# DCMv3.net
KiCad netlist of a schematic drawn in EAGLE
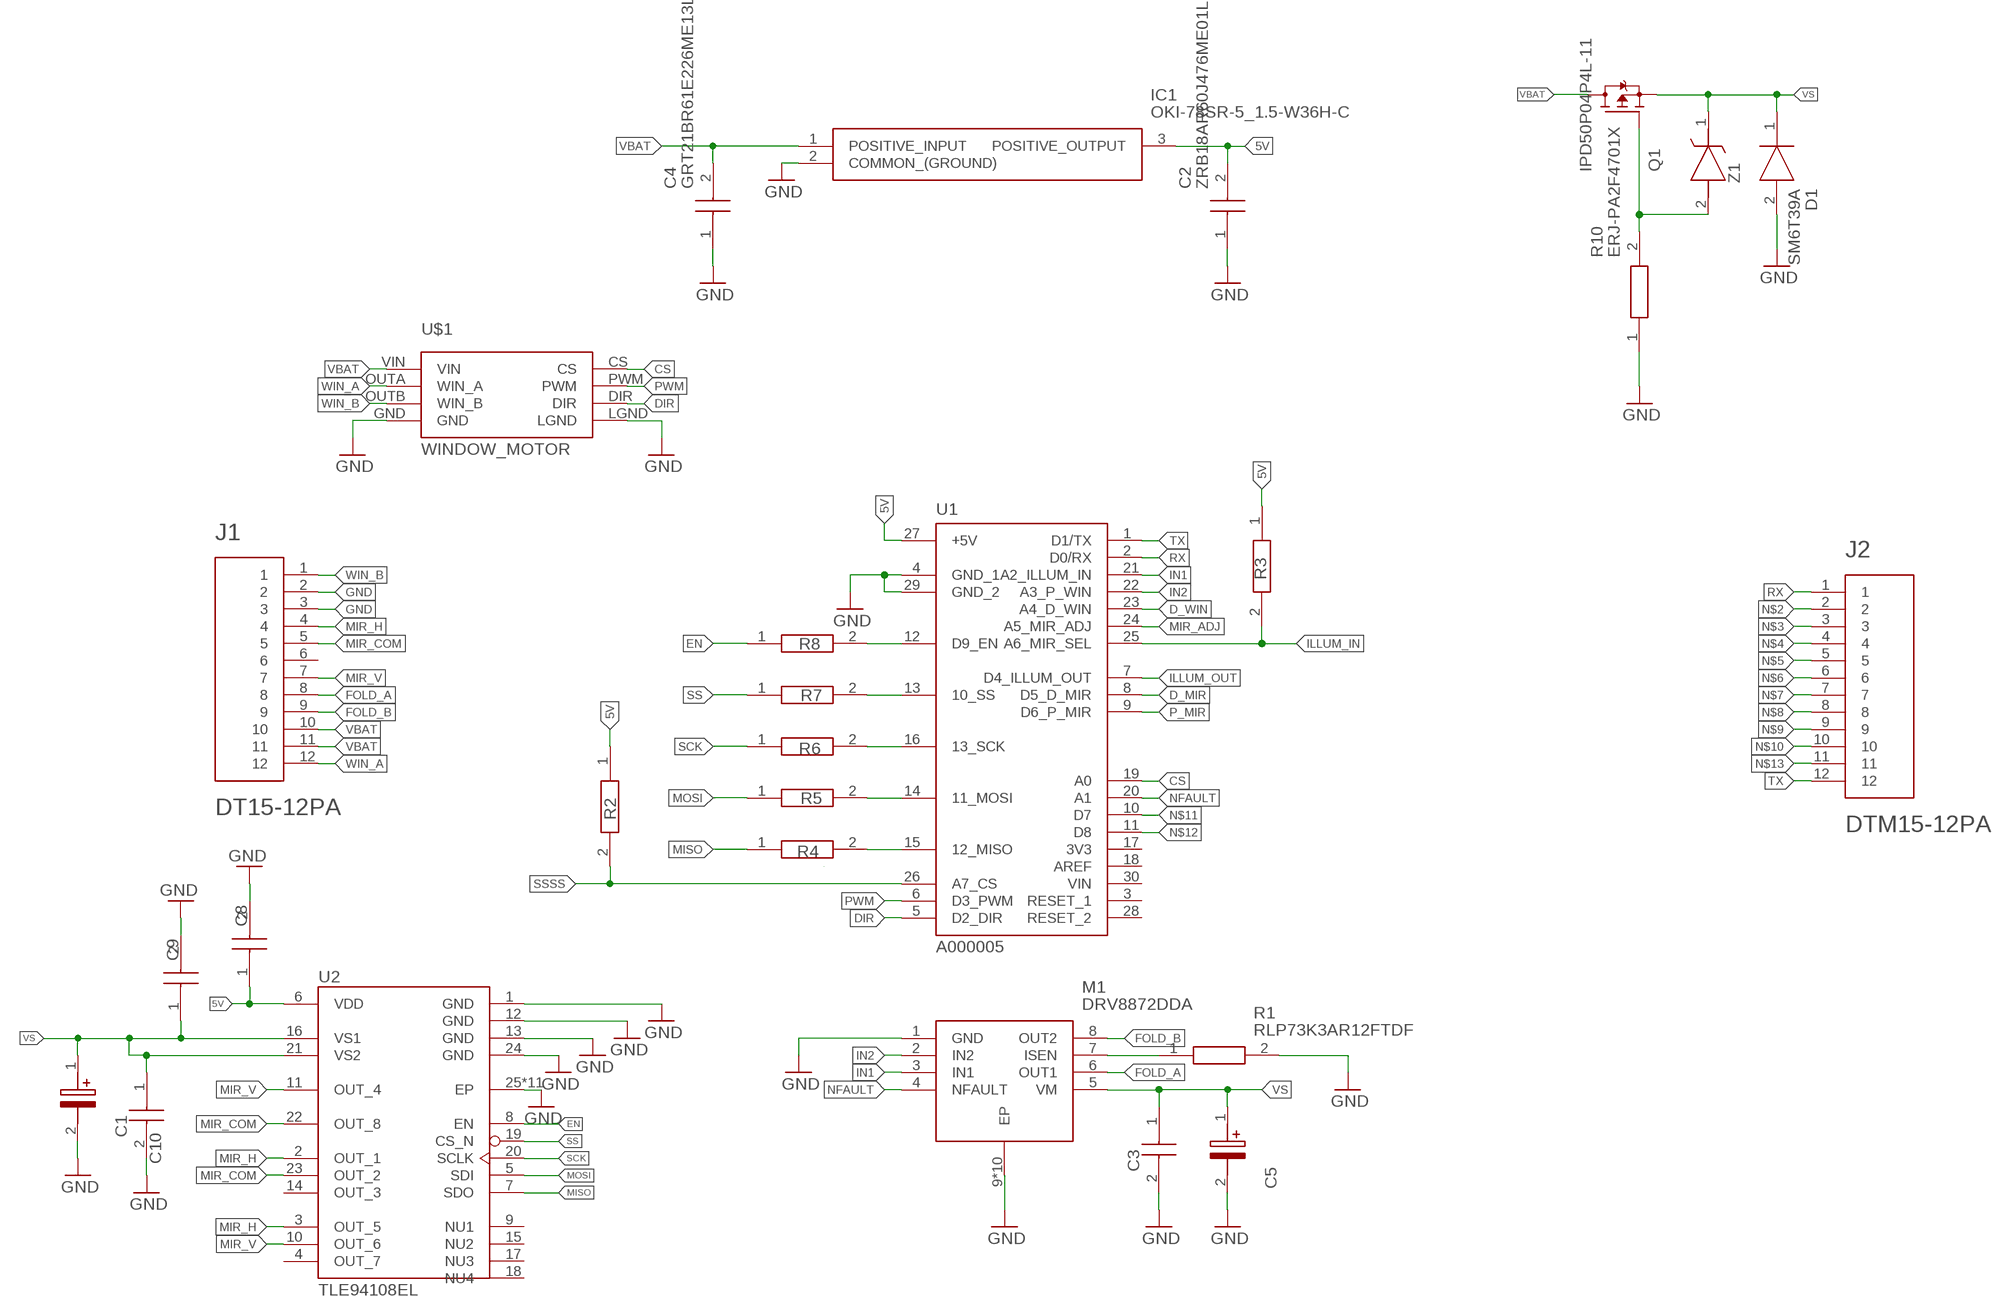
[diagram p0: schematic, sheet 1]

(export (version "E")
  (design (tool "Eeschema 10.0.6"))
  (components
    (comp (ref "C1")
      (value "EEE-FT1H470AP")
      (footprint "eagle-import:CAPAE660X610N")
      (fields (field (name "MOUSER_PART_NUMBER") "667-EEE-FT1H470AP"))
      (libsource (lib "eagle-import") (part "EEE-FT1H470AP"))
    )
    (comp (ref "C2")
      (value "ZRB18AR60J476ME01L")
      (footprint "eagle-import:CAPC1608X120N")
      (fields (field (name "MOUSER_PART_NUMBER") "81-ZRB18AR60J476ME1L"))
      (libsource (lib "eagle-import") (part "ZRB18AR60J476ME01L"))
    )
    (comp (ref "C3")
      (value "GRM033R6YA104KE14D")
      (footprint "eagle-import:CAPC0603X33N")
      (fields (field (name "MOUSER_PART_NUMBER") "81-GRM33R6YA104KE14D"))
      (libsource (lib "eagle-import") (part "GRM033R6YA104KE14D"))
    )
    (comp (ref "C4")
      (value "GRT21BR61E226ME13L")
      (footprint "eagle-import:CAPC2012X145N")
      (fields (field (name "MOUSER_PART_NUMBER") "81-GRT21BR61E226ME3L"))
      (libsource (lib "eagle-import") (part "GRT21BR61E226ME13L"))
    )
    (comp (ref "C5")
      (value "EEE-FT1H470AP")
      (footprint "eagle-import:CAPAE660X610N")
      (fields (field (name "MOUSER_PART_NUMBER") "667-EEE-FT1H470AP"))
      (libsource (lib "eagle-import") (part "EEE-FT1H470AP"))
    )
    (comp (ref "C8")
      (value "GRM155R61H104JE14D")
      (footprint "eagle-import:CAPC1005X55N")
      (fields (field (name "MOUSER_PART_NUMBER") "81-GRM155R61H104JE4D"))
      (libsource (lib "eagle-import") (part "GRM155R61H104JE14D"))
    )
    (comp (ref "C9")
      (value "GRM155R61H104JE14D")
      (footprint "eagle-import:CAPC1005X55N")
      (fields (field (name "MOUSER_PART_NUMBER") "81-GRM155R61H104JE4D"))
      (libsource (lib "eagle-import") (part "GRM155R61H104JE14D"))
    )
    (comp (ref "C10")
      (value "GRM155R61H104JE14D")
      (footprint "eagle-import:CAPC1005X55N")
      (fields (field (name "MOUSER_PART_NUMBER") "81-GRM155R61H104JE4D"))
      (libsource (lib "eagle-import") (part "GRM155R61H104JE14D"))
    )
    (comp (ref "D1")
      (value "SM6T39A")
      (footprint "eagle-import:DIOM5436X265N")
      (fields (field (name "MOUSER_PART_NUMBER") "511-SM6T39A"))
      (libsource (lib "eagle-import") (part "SM6T39A"))
    )
    (comp (ref "IC1")
      (value "OKI-78SR-5_1.5-W36H-C")
      (footprint "eagle-import:OKI-78SR-HORIZONTAL")
      (fields
        (field (name "MANUFACTURER_PART_NUMBER") "OKI-78SR-5/1.5-W36H-C")
        (field (name "MOUSER_PART_NUMBER") "580-OKI78SR51.5W36HC")
      )
      (libsource (lib "eagle-import") (part "OKI-78SR-5_1.5-W36H-C"))
    )
    (comp (ref "J1")
      (value "DT15-12PA")
      (footprint "eagle-import:TE_DT15-12PA")
      (fields (field (name "MF") "TE Connectivity"))
      (libsource (lib "eagle-import") (part "DT15-12PA"))
    )
    (comp (ref "J2")
      (value "DTM15-12PA")
      (footprint "eagle-import:TE_DTM15-12PA")
      (fields (field (name "MF") "TE Connectivity") (field (name "MPN") "DTM15-12PA "))
      (libsource (lib "eagle-import") (part "DTM15-12PA"))
    )
    (comp (ref "M1")
      (value "DRV8872DDA")
      (footprint "eagle-import:SOIC127P600X170-9N")
      (fields (field (name "MOUSER_PART_NUMBER") "595-DRV8872DDA"))
      (libsource (lib "eagle-import") (part "DRV8872DDA"))
    )
    (comp (ref "Q1")
      (value "IPD50P04P4L-11")
      (footprint "eagle-import:DPAK228P998X235-3N")
      (fields (field (name "MF") "Infineon Technologies"))
      (libsource (lib "eagle-import") (part "IPD50P04P4L-11"))
    )
    (comp (ref "R1")
      (value "RLP73K3AR12FTDF")
      (footprint "eagle-import:RESC6432X84N")
      (libsource (lib "eagle-import") (part "RLP73K3AR12FTDF"))
    )
    (comp (ref "R2")
      (value "ERJ-1RHD2202C")
      (footprint "eagle-import:RESC0603X26N")
      (libsource (lib "eagle-import") (part "ERJ-1RHD2202C"))
    )
    (comp (ref "R3")
      (value "ERJ-1RHD2202C")
      (footprint "eagle-import:RESC0603X26N")
      (libsource (lib "eagle-import") (part "ERJ-1RHD2202C"))
    )
    (comp (ref "R4")
      (value "ERJ-1RKD4700C")
      (footprint "eagle-import:RESC0603X26N")
      (libsource (lib "eagle-import") (part "ERJ-1RKD4700C"))
    )
    (comp (ref "R5")
      (value "ERJ-1RKD4700C")
      (footprint "eagle-import:RESC0603X26N")
      (libsource (lib "eagle-import") (part "ERJ-1RKD4700C"))
    )
    (comp (ref "R6")
      (value "ERJ-1RKD4700C")
      (footprint "eagle-import:RESC0603X26N")
      (libsource (lib "eagle-import") (part "ERJ-1RKD4700C"))
    )
    (comp (ref "R7")
      (value "ERJ-1RKD4700C")
      (footprint "eagle-import:RESC0603X26N")
      (libsource (lib "eagle-import") (part "ERJ-1RKD4700C"))
    )
    (comp (ref "R8")
      (value "ERJ-1RKD4700C")
      (footprint "eagle-import:RESC0603X26N")
      (libsource (lib "eagle-import") (part "ERJ-1RKD4700C"))
    )
    (comp (ref "R10")
      (value "ERJ-PA2F4701X")
      (footprint "eagle-import:RESC1005X40N")
      (libsource (lib "eagle-import") (part "ERJ-PA2F4701X"))
    )
    (comp (ref "U$1")
      (value "WINDOW_MOTOR")
      (footprint "eagle-import:POLOLU")
      (libsource (lib "eagle-import") (part "WINDOW_MOTOR"))
    )
    (comp (ref "U1")
      (value "A000005")
      (footprint "eagle-import:ARDUINO_A000005")
      (fields (field (name "MF") "Arduino"))
      (libsource (lib "eagle-import") (part "A000005"))
    )
    (comp (ref "U2")
      (value "TLE94108EL")
      (footprint "eagle-import:SOP65P600X170-25N")
      (libsource (lib "eagle-import") (part "TLE94108EL"))
    )
    (comp (ref "Z1")
      (value "MM3Z12VT1G")
      (footprint "eagle-import:SOD2512X110N")
      (fields (field (name "MOUSER_PART_NUMBER") "863-MM3Z12VT1G"))
      (libsource (lib "eagle-import") (part "MM3Z12VT1G"))
    )
  )
  (nets
    (net (code "1") (name "5V") (class "Default")
      (node (ref "C2") (pin "2") (pinfunction "2_2") (pintype "bidirectional"))
      (node (ref "C8") (pin "1") (pinfunction "1_1") (pintype "bidirectional"))
      (node (ref "IC1") (pin "3") (pinfunction "POSITIVE_OUTPUT_3") (pintype "output"))
      (node (ref "R2") (pin "1") (pinfunction "1_1") (pintype "bidirectional"))
      (node (ref "R3") (pin "1") (pinfunction "1_1") (pintype "bidirectional"))
      (node (ref "U1") (pin "27") (pinfunction "+5V_27") (pintype "power_in"))
      (node (ref "U2") (pin "6") (pinfunction "VDD_6") (pintype "power_in"))
    )
    (net (code "2") (name "CS") (class "Default")
      (node (ref "U$1") (pin "CS") (pinfunction "CS_CS") (pintype "output"))
      (node (ref "U1") (pin "19") (pinfunction "A0_19") (pintype "passive"))
    )
    (net (code "3") (name "DIR") (class "Default")
      (node (ref "U$1") (pin "DIR") (pinfunction "DIR_DIR") (pintype "input"))
      (node (ref "U1") (pin "5") (pinfunction "D2_DIR_5") (pintype "output"))
    )
    (net (code "4") (name "D_MIR") (class "Default")
      (node (ref "U1") (pin "8") (pinfunction "D5_D_MIR_8") (pintype "output"))
    )
    (net (code "5") (name "D_WIN") (class "Default")
      (node (ref "U1") (pin "23") (pinfunction "A4_D_WIN_23") (pintype "input"))
    )
    (net (code "6") (name "EN") (class "Default")
      (node (ref "R8") (pin "1") (pinfunction "1_1") (pintype "bidirectional"))
      (node (ref "U2") (pin "8") (pinfunction "EN_8") (pintype "input"))
    )
    (net (code "7") (name "FOLD_A") (class "Default")
      (node (ref "J1") (pin "8") (pinfunction "8_8") (pintype "passive"))
      (node (ref "M1") (pin "6") (pinfunction "OUT1_6") (pintype "output"))
    )
    (net (code "8") (name "FOLD_B") (class "Default")
      (node (ref "J1") (pin "9") (pinfunction "9_9") (pintype "passive"))
      (node (ref "M1") (pin "8") (pinfunction "OUT2_8") (pintype "output"))
    )
    (net (code "9") (name "GND") (class "Default")
      (node (ref "C1") (pin "2") (pinfunction "-_2") (pintype "bidirectional"))
      (node (ref "C10") (pin "2") (pinfunction "2_2") (pintype "bidirectional"))
      (node (ref "C2") (pin "1") (pinfunction "1_1") (pintype "bidirectional"))
      (node (ref "C3") (pin "2") (pinfunction "2_2") (pintype "bidirectional"))
      (node (ref "C4") (pin "1") (pinfunction "1_1") (pintype "bidirectional"))
      (node (ref "C5") (pin "2") (pinfunction "-_2") (pintype "bidirectional"))
      (node (ref "C8") (pin "2") (pinfunction "2_2") (pintype "bidirectional"))
      (node (ref "C9") (pin "2") (pinfunction "2_2") (pintype "bidirectional"))
      (node (ref "D1") (pin "2") (pinfunction "A_2") (pintype "bidirectional"))
      (node (ref "IC1") (pin "2") (pinfunction "COMMON_(GROUND)_2") (pintype "bidirectional"))
      (node (ref "J1") (pin "2") (pinfunction "2_2") (pintype "passive"))
      (node (ref "J1") (pin "3") (pinfunction "3_3") (pintype "passive"))
      (node (ref "M1") (pin "1") (pinfunction "GND_1") (pintype "power_in"))
      (node (ref "M1") (pin "9") (pinfunction "EP_9") (pintype "bidirectional"))
      (node (ref "M1") (pin "P$1") (pinfunction "EP_P$1") (pintype "bidirectional"))
      (node (ref "M1") (pin "P$2") (pinfunction "EP_P$2") (pintype "bidirectional"))
      (node (ref "M1") (pin "P$3") (pinfunction "EP_P$3") (pintype "bidirectional"))
      (node (ref "M1") (pin "P$4") (pinfunction "EP_P$4") (pintype "bidirectional"))
      (node (ref "M1") (pin "P$5") (pinfunction "EP_P$5") (pintype "bidirectional"))
      (node (ref "M1") (pin "P$6") (pinfunction "EP_P$6") (pintype "bidirectional"))
      (node (ref "M1") (pin "P$7") (pinfunction "EP_P$7") (pintype "bidirectional"))
      (node (ref "M1") (pin "P$8") (pinfunction "EP_P$8") (pintype "bidirectional"))
      (node (ref "M1") (pin "P$9") (pinfunction "EP_P$9") (pintype "bidirectional"))
      (node (ref "R1") (pin "2") (pinfunction "2_2") (pintype "bidirectional"))
      (node (ref "R10") (pin "1") (pinfunction "1_1") (pintype "bidirectional"))
      (node (ref "U$1") (pin "GND") (pinfunction "GND_GND") (pintype "power_in"))
      (node (ref "U$1") (pin "LGND") (pinfunction "LGND_LGND") (pintype "power_in"))
      (node (ref "U1") (pin "29") (pinfunction "GND_2_29") (pintype "power_in"))
      (node (ref "U1") (pin "4") (pinfunction "GND_1_4") (pintype "power_in"))
      (node (ref "U2") (pin "1") (pinfunction "GND_1") (pintype "power_in"))
      (node (ref "U2") (pin "12") (pinfunction "GND_12") (pintype "power_in"))
      (node (ref "U2") (pin "13") (pinfunction "GND_13") (pintype "power_in"))
      (node (ref "U2") (pin "24") (pinfunction "GND_24") (pintype "power_in"))
      (node (ref "U2") (pin "25") (pinfunction "EP_25") (pintype "power_in"))
      (node (ref "U2") (pin "GND") (pinfunction "EP_GND") (pintype "power_in"))
      (node (ref "U2") (pin "GND1") (pinfunction "EP_GND1") (pintype "power_in"))
      (node (ref "U2") (pin "GND2") (pinfunction "EP_GND2") (pintype "power_in"))
      (node (ref "U2") (pin "GND3") (pinfunction "EP_GND3") (pintype "power_in"))
      (node (ref "U2") (pin "GND4") (pinfunction "EP_GND4") (pintype "power_in"))
      (node (ref "U2") (pin "GND5") (pinfunction "EP_GND5") (pintype "power_in"))
      (node (ref "U2") (pin "GND6") (pinfunction "EP_GND6") (pintype "power_in"))
      (node (ref "U2") (pin "GND7") (pinfunction "EP_GND7") (pintype "power_in"))
      (node (ref "U2") (pin "GND8") (pinfunction "EP_GND8") (pintype "power_in"))
      (node (ref "U2") (pin "GND9") (pinfunction "EP_GND9") (pintype "power_in"))
    )
    (net (code "10") (name "ILLUM_IN") (class "Default")
      (node (ref "R3") (pin "2") (pinfunction "2_2") (pintype "bidirectional"))
      (node (ref "U1") (pin "25") (pinfunction "A6_MIR_SEL_25") (pintype "input"))
    )
    (net (code "11") (name "ILLUM_OUT") (class "Default")
      (node (ref "U1") (pin "7") (pinfunction "D4_ILLUM_OUT_7") (pintype "output"))
    )
    (net (code "12") (name "IN1") (class "Default")
      (node (ref "M1") (pin "3") (pinfunction "IN1_3") (pintype "input"))
      (node (ref "U1") (pin "21") (pinfunction "A2_ILLUM_IN_21") (pintype "passive"))
    )
    (net (code "13") (name "IN2") (class "Default")
      (node (ref "M1") (pin "2") (pinfunction "IN2_2") (pintype "input"))
      (node (ref "U1") (pin "22") (pinfunction "A3_P_WIN_22") (pintype "input"))
    )
    (net (code "14") (name "MIR_ADJ") (class "Default")
      (node (ref "U1") (pin "24") (pinfunction "A5_MIR_ADJ_24") (pintype "input"))
    )
    (net (code "15") (name "MIR_COM") (class "Default")
      (node (ref "J1") (pin "5") (pinfunction "5_5") (pintype "passive"))
      (node (ref "U2") (pin "22") (pinfunction "OUT_8_22") (pintype "bidirectional"))
      (node (ref "U2") (pin "23") (pinfunction "OUT_2_23") (pintype "bidirectional"))
    )
    (net (code "16") (name "MIR_H") (class "Default")
      (node (ref "J1") (pin "4") (pinfunction "4_4") (pintype "passive"))
      (node (ref "U2") (pin "2") (pinfunction "OUT_1_2") (pintype "bidirectional"))
      (node (ref "U2") (pin "3") (pinfunction "OUT_5_3") (pintype "bidirectional"))
    )
    (net (code "17") (name "MIR_V") (class "Default")
      (node (ref "J1") (pin "7") (pinfunction "7_7") (pintype "passive"))
      (node (ref "U2") (pin "10") (pinfunction "OUT_6_10") (pintype "bidirectional"))
      (node (ref "U2") (pin "11") (pinfunction "OUT_4_11") (pintype "bidirectional"))
    )
    (net (code "18") (name "MISO") (class "Default")
      (node (ref "R4") (pin "1") (pinfunction "1_1") (pintype "bidirectional"))
      (node (ref "U2") (pin "7") (pinfunction "SDO_7") (pintype "output"))
    )
    (net (code "19") (name "MOSI") (class "Default")
      (node (ref "R5") (pin "1") (pinfunction "1_1") (pintype "bidirectional"))
      (node (ref "U2") (pin "5") (pinfunction "SDI_5") (pintype "input"))
    )
    (net (code "20") (name "N$2") (class "Default")
      (node (ref "J2") (pin "2") (pinfunction "2_2") (pintype "passive"))
    )
    (net (code "21") (name "N$3") (class "Default")
      (node (ref "J2") (pin "3") (pinfunction "3_3") (pintype "passive"))
    )
    (net (code "22") (name "N$4") (class "Default")
      (node (ref "J2") (pin "4") (pinfunction "4_4") (pintype "passive"))
    )
    (net (code "23") (name "N$5") (class "Default")
      (node (ref "J2") (pin "5") (pinfunction "5_5") (pintype "passive"))
    )
    (net (code "24") (name "N$6") (class "Default")
      (node (ref "J2") (pin "6") (pinfunction "6_6") (pintype "passive"))
    )
    (net (code "25") (name "N$7") (class "Default")
      (node (ref "J2") (pin "7") (pinfunction "7_7") (pintype "passive"))
    )
    (net (code "26") (name "N$8") (class "Default")
      (node (ref "J2") (pin "8") (pinfunction "8_8") (pintype "passive"))
    )
    (net (code "27") (name "N$9") (class "Default")
      (node (ref "J2") (pin "9") (pinfunction "9_9") (pintype "passive"))
    )
    (net (code "28") (name "N$10") (class "Default")
      (node (ref "J2") (pin "10") (pinfunction "10_10") (pintype "passive"))
    )
    (net (code "29") (name "N$11") (class "Default")
      (node (ref "U1") (pin "10") (pinfunction "D7_10") (pintype "output"))
    )
    (net (code "30") (name "N$12") (class "Default")
      (node (ref "U1") (pin "11") (pinfunction "D8_11") (pintype "passive"))
    )
    (net (code "31") (name "N$13") (class "Default")
      (node (ref "J2") (pin "11") (pinfunction "11_11") (pintype "passive"))
    )
    (net (code "32") (name "NFAULT") (class "Default")
      (node (ref "M1") (pin "4") (pinfunction "NFAULT_4") (pintype "output"))
      (node (ref "U1") (pin "20") (pinfunction "A1_20") (pintype "passive"))
    )
    (net (code "33") (name "Net-(M1-ISEN)") (class "Default")
      (node (ref "M1") (pin "7") (pinfunction "ISEN_7") (pintype "power_in"))
      (node (ref "R1") (pin "1") (pinfunction "1_1") (pintype "bidirectional"))
    )
    (net (code "34") (name "Net-(Q1-G)") (class "Default")
      (node (ref "Q1") (pin "1") (pinfunction "G_1") (pintype "passive"))
      (node (ref "R10") (pin "2") (pinfunction "2_2") (pintype "bidirectional"))
      (node (ref "Z1") (pin "2") (pinfunction "A_2") (pintype "bidirectional"))
    )
    (net (code "35") (name "Net-(U1-10_SS)") (class "Default")
      (node (ref "R7") (pin "2") (pinfunction "2_2") (pintype "bidirectional"))
      (node (ref "U1") (pin "13") (pinfunction "10_SS_13") (pintype "output"))
    )
    (net (code "36") (name "Net-(U1-11_MOSI)") (class "Default")
      (node (ref "R5") (pin "2") (pinfunction "2_2") (pintype "bidirectional"))
      (node (ref "U1") (pin "14") (pinfunction "11_MOSI_14") (pintype "output"))
    )
    (net (code "37") (name "Net-(U1-12_MISO)") (class "Default")
      (node (ref "R4") (pin "2") (pinfunction "2_2") (pintype "bidirectional"))
      (node (ref "U1") (pin "15") (pinfunction "12_MISO_15") (pintype "input"))
    )
    (net (code "38") (name "Net-(U1-13_SCK)") (class "Default")
      (node (ref "R6") (pin "2") (pinfunction "2_2") (pintype "bidirectional"))
      (node (ref "U1") (pin "16") (pinfunction "13_SCK_16") (pintype "output"))
    )
    (net (code "39") (name "Net-(U1-D9_EN)") (class "Default")
      (node (ref "R8") (pin "2") (pinfunction "2_2") (pintype "bidirectional"))
      (node (ref "U1") (pin "12") (pinfunction "D9_EN_12") (pintype "output"))
    )
    (net (code "40") (name "PWM") (class "Default")
      (node (ref "U$1") (pin "PWM") (pinfunction "PWM_PWM") (pintype "input"))
      (node (ref "U1") (pin "6") (pinfunction "D3_PWM_6") (pintype "output"))
    )
    (net (code "41") (name "P_MIR") (class "Default")
      (node (ref "U1") (pin "9") (pinfunction "D6_P_MIR_9") (pintype "output"))
    )
    (net (code "42") (name "RX") (class "Default")
      (node (ref "J2") (pin "1") (pinfunction "1_1") (pintype "passive"))
      (node (ref "U1") (pin "2") (pinfunction "D0/RX_2") (pintype "input"))
    )
    (net (code "43") (name "SCK") (class "Default")
      (node (ref "R6") (pin "1") (pinfunction "1_1") (pintype "bidirectional"))
      (node (ref "U2") (pin "20") (pinfunction "SCLK_20") (pintype "input"))
    )
    (net (code "44") (name "SS") (class "Default")
      (node (ref "R7") (pin "1") (pinfunction "1_1") (pintype "bidirectional"))
      (node (ref "U2") (pin "19") (pinfunction "CS_N_19") (pintype "input"))
    )
    (net (code "45") (name "SSSS") (class "Default")
      (node (ref "R2") (pin "2") (pinfunction "2_2") (pintype "bidirectional"))
      (node (ref "U1") (pin "26") (pinfunction "A7_CS_26") (pintype "input"))
    )
    (net (code "46") (name "TX") (class "Default")
      (node (ref "J2") (pin "12") (pinfunction "12_12") (pintype "passive"))
      (node (ref "U1") (pin "1") (pinfunction "D1/TX_1") (pintype "output"))
    )
    (net (code "47") (name "VBAT") (class "Default")
      (node (ref "C4") (pin "2") (pinfunction "2_2") (pintype "bidirectional"))
      (node (ref "IC1") (pin "1") (pinfunction "POSITIVE_INPUT_1") (pintype "input"))
      (node (ref "J1") (pin "10") (pinfunction "10_10") (pintype "passive"))
      (node (ref "J1") (pin "11") (pinfunction "11_11") (pintype "passive"))
      (node (ref "Q1") (pin "2") (pinfunction "D_2") (pintype "passive"))
      (node (ref "U$1") (pin "VIN") (pinfunction "VIN_VIN") (pintype "power_in"))
    )
    (net (code "48") (name "VS") (class "Default")
      (node (ref "C1") (pin "1") (pinfunction "+_1") (pintype "bidirectional"))
      (node (ref "C10") (pin "1") (pinfunction "1_1") (pintype "bidirectional"))
      (node (ref "C3") (pin "1") (pinfunction "1_1") (pintype "bidirectional"))
      (node (ref "C5") (pin "1") (pinfunction "+_1") (pintype "bidirectional"))
      (node (ref "C9") (pin "1") (pinfunction "1_1") (pintype "bidirectional"))
      (node (ref "D1") (pin "1") (pinfunction "K_1") (pintype "bidirectional"))
      (node (ref "M1") (pin "5") (pinfunction "VM_5") (pintype "power_in"))
      (node (ref "Q1") (pin "3") (pinfunction "S_3") (pintype "passive"))
      (node (ref "U2") (pin "16") (pinfunction "VS1_16") (pintype "power_in"))
      (node (ref "U2") (pin "21") (pinfunction "VS2_21") (pintype "power_in"))
      (node (ref "Z1") (pin "1") (pinfunction "K_1") (pintype "bidirectional"))
    )
    (net (code "49") (name "WIN_A") (class "Default")
      (node (ref "J1") (pin "12") (pinfunction "12_12") (pintype "passive"))
      (node (ref "U$1") (pin "OUTA") (pinfunction "WIN_A_OUTA") (pintype "output"))
    )
    (net (code "50") (name "WIN_B") (class "Default")
      (node (ref "J1") (pin "1") (pinfunction "1_1") (pintype "passive"))
      (node (ref "U$1") (pin "OUTB") (pinfunction "WIN_B_OUTB") (pintype "output"))
    )
    (net (code "51") (name "unconnected-(J1-Pad6)") (class "Default")
      (node (ref "J1") (pin "6") (pinfunction "6_6") (pintype "passive"))
    )
    (net (code "52") (name "unconnected-(U1-3V3-Pad17)") (class "Default")
      (node (ref "U1") (pin "17") (pinfunction "3V3_17") (pintype "passive"))
    )
    (net (code "53") (name "unconnected-(U1-AREF-Pad18)") (class "Default")
      (node (ref "U1") (pin "18") (pinfunction "AREF_18") (pintype "passive"))
    )
    (net (code "54") (name "unconnected-(U1-RESET_1-Pad3)") (class "Default")
      (node (ref "U1") (pin "3") (pinfunction "RESET_1_3") (pintype "passive"))
    )
    (net (code "55") (name "unconnected-(U1-RESET_2-Pad28)") (class "Default")
      (node (ref "U1") (pin "28") (pinfunction "RESET_2_28") (pintype "passive"))
    )
    (net (code "56") (name "unconnected-(U1-VIN-Pad30)") (class "Default")
      (node (ref "U1") (pin "30") (pinfunction "VIN_30") (pintype "passive"))
    )
    (net (code "57") (name "unconnected-(U2-NU1-Pad9)") (class "Default")
      (node (ref "U2") (pin "9") (pinfunction "NU1_9") (pintype "passive"))
    )
    (net (code "58") (name "unconnected-(U2-NU2-Pad15)") (class "Default")
      (node (ref "U2") (pin "15") (pinfunction "NU2_15") (pintype "passive"))
    )
    (net (code "59") (name "unconnected-(U2-NU3-Pad17)") (class "Default")
      (node (ref "U2") (pin "17") (pinfunction "NU3_17") (pintype "passive"))
    )
    (net (code "60") (name "unconnected-(U2-NU4-Pad18)") (class "Default")
      (node (ref "U2") (pin "18") (pinfunction "NU4_18") (pintype "passive"))
    )
    (net (code "61") (name "unconnected-(U2-OUT_3-Pad14)") (class "Default")
      (node (ref "U2") (pin "14") (pinfunction "OUT_3_14") (pintype "bidirectional"))
    )
    (net (code "62") (name "unconnected-(U2-OUT_7-Pad4)") (class "Default")
      (node (ref "U2") (pin "4") (pinfunction "OUT_7_4") (pintype "bidirectional"))
    )
  )
)
